# proto.net
KiCad netlist of a schematic drawn in EAGLE
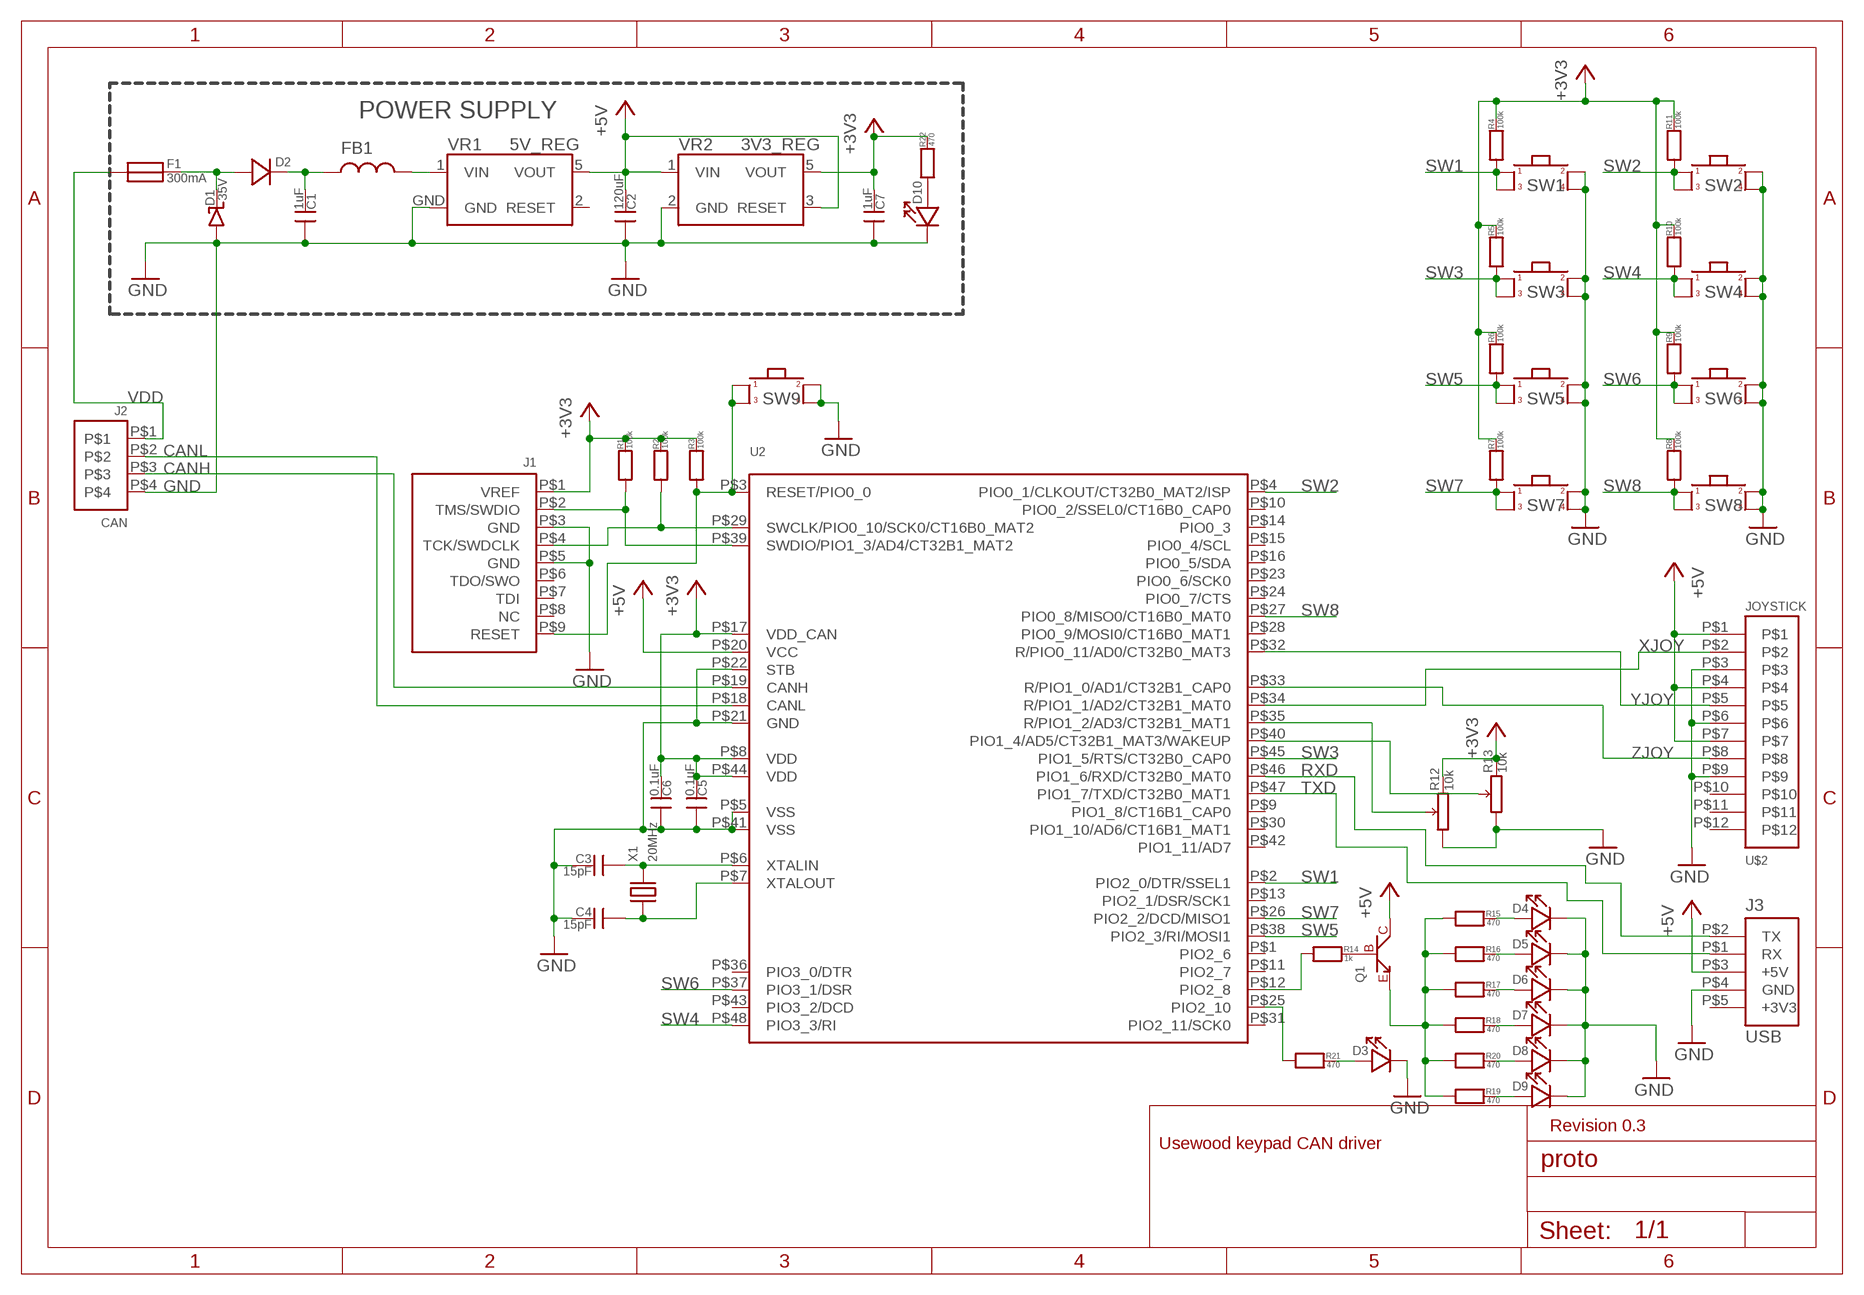
[diagram p0: schematic, sheet 1]

(export (version "E")
  (design (tool "Eeschema 10.0.6"))
  (components
    (comp (ref "C1")
      (value "1uF")
      (footprint "eagle-import:0603")
      (libsource (lib "eagle-import") (part "CAP0603"))
    )
    (comp (ref "C2")
      (value "120uF")
      (footprint "eagle-import:0603")
      (libsource (lib "eagle-import") (part "CAP0603"))
    )
    (comp (ref "C3")
      (value "15pF")
      (footprint "eagle-import:0603")
      (libsource (lib "eagle-import") (part "CAP0603"))
    )
    (comp (ref "C4")
      (value "15pF")
      (footprint "eagle-import:0603")
      (libsource (lib "eagle-import") (part "CAP0603"))
    )
    (comp (ref "C5")
      (value "0.1uF")
      (footprint "eagle-import:0603")
      (libsource (lib "eagle-import") (part "CAP0603"))
    )
    (comp (ref "C6")
      (value "0.1uF")
      (footprint "eagle-import:0603")
      (libsource (lib "eagle-import") (part "CAP0603"))
    )
    (comp (ref "C7")
      (value "1uF")
      (footprint "eagle-import:0603")
      (libsource (lib "eagle-import") (part "CAP0603"))
    )
    (comp (ref "D1")
      (value "35V")
      (footprint "eagle-import:DO-214AB")
      (libsource (lib "eagle-import") (part "DIODE_TVSDO-214AA"))
    )
    (comp (ref "D2")
      (value "DIODEDO219AB")
      (footprint "eagle-import:DO219AB")
      (libsource (lib "eagle-import") (part "DIODEDO219AB"))
    )
    (comp (ref "D3")
      (value "LED0603")
      (footprint "eagle-import:0603")
      (libsource (lib "eagle-import") (part "LED0603"))
    )
    (comp (ref "D4")
      (value "LED0603")
      (footprint "eagle-import:0603")
      (libsource (lib "eagle-import") (part "LED0603"))
    )
    (comp (ref "D5")
      (value "LED0603")
      (footprint "eagle-import:0603")
      (libsource (lib "eagle-import") (part "LED0603"))
    )
    (comp (ref "D6")
      (value "LED0603")
      (footprint "eagle-import:0603")
      (libsource (lib "eagle-import") (part "LED0603"))
    )
    (comp (ref "D7")
      (value "LED0603")
      (footprint "eagle-import:0603")
      (libsource (lib "eagle-import") (part "LED0603"))
    )
    (comp (ref "D8")
      (value "LED0603")
      (footprint "eagle-import:0603")
      (libsource (lib "eagle-import") (part "LED0603"))
    )
    (comp (ref "D9")
      (value "LED0603")
      (footprint "eagle-import:0603")
      (libsource (lib "eagle-import") (part "LED0603"))
    )
    (comp (ref "D10")
      (value "LED0603")
      (footprint "eagle-import:0603")
      (libsource (lib "eagle-import") (part "LED0603"))
    )
    (comp (ref "F1")
      (value "300mA")
      (footprint "eagle-import:FUSE_100MA")
      (libsource (lib "eagle-import") (part "FUSE100MA"))
    )
    (comp (ref "FB1")
      (value "FERRITE0603")
      (footprint "eagle-import:0603")
      (libsource (lib "eagle-import") (part "FERRITE0603"))
    )
    (comp (ref "J1")
      (value "ARM_JTAG/SWD_HEADER_10_PINSMD")
      (footprint "eagle-import:ARM_10_PIN_JTAG_SWD_CONNECTOR")
      (libsource (lib "eagle-import") (part "ARM_JTAG/SWD_HEADER_10_PINSMD"))
    )
    (comp (ref "J2")
      (value "CAN")
      (footprint "eagle-import:MOLEX_MICRO-FIT_4WAY")
      (libsource (lib "eagle-import") (part "MOLEX_MICRO-FIT_4WAYTH"))
    )
    (comp (ref "J3")
      (value "USB")
      (footprint "eagle-import:HEADER5_1")
      (libsource (lib "eagle-import") (part "HEADER_USARTTH"))
    )
    (comp (ref "Q1")
      (value "NPN_TRANSISTORSOT323")
      (footprint "eagle-import:SOT323")
      (libsource (lib "eagle-import") (part "NPN_TRANSISTORSOT323"))
    )
    (comp (ref "R1")
      (value "100k")
      (footprint "eagle-import:0603")
      (libsource (lib "eagle-import") (part "RES0603"))
    )
    (comp (ref "R2")
      (value "100k")
      (footprint "eagle-import:0603")
      (libsource (lib "eagle-import") (part "RES0603"))
    )
    (comp (ref "R3")
      (value "100k")
      (footprint "eagle-import:0603")
      (libsource (lib "eagle-import") (part "RES0603"))
    )
    (comp (ref "R4")
      (value "100k")
      (footprint "eagle-import:0603")
      (libsource (lib "eagle-import") (part "RES0603"))
    )
    (comp (ref "R5")
      (value "100k")
      (footprint "eagle-import:0603")
      (libsource (lib "eagle-import") (part "RES0603"))
    )
    (comp (ref "R6")
      (value "100k")
      (footprint "eagle-import:0603")
      (libsource (lib "eagle-import") (part "RES0603"))
    )
    (comp (ref "R7")
      (value "100k")
      (footprint "eagle-import:0603")
      (libsource (lib "eagle-import") (part "RES0603"))
    )
    (comp (ref "R8")
      (value "100k")
      (footprint "eagle-import:0603")
      (libsource (lib "eagle-import") (part "RES0603"))
    )
    (comp (ref "R9")
      (value "100k")
      (footprint "eagle-import:0603")
      (libsource (lib "eagle-import") (part "RES0603"))
    )
    (comp (ref "R10")
      (value "100k")
      (footprint "eagle-import:0603")
      (libsource (lib "eagle-import") (part "RES0603"))
    )
    (comp (ref "R11")
      (value "100k")
      (footprint "eagle-import:0603")
      (libsource (lib "eagle-import") (part "RES0603"))
    )
    (comp (ref "R12")
      (value "10k")
      (footprint "eagle-import:RES_POT_RK09K1130C94")
      (libsource (lib "eagle-import") (part "RES_POTRK09K1130C94"))
    )
    (comp (ref "R13")
      (value "10k")
      (footprint "eagle-import:RES_POT_RK09K1130C94")
      (libsource (lib "eagle-import") (part "RES_POTRK09K1130C94"))
    )
    (comp (ref "R14")
      (value "1k")
      (footprint "eagle-import:0603")
      (libsource (lib "eagle-import") (part "RES0603"))
    )
    (comp (ref "R15")
      (value "470")
      (footprint "eagle-import:0603")
      (libsource (lib "eagle-import") (part "RES0603"))
    )
    (comp (ref "R16")
      (value "470")
      (footprint "eagle-import:0603")
      (libsource (lib "eagle-import") (part "RES0603"))
    )
    (comp (ref "R17")
      (value "470")
      (footprint "eagle-import:0603")
      (libsource (lib "eagle-import") (part "RES0603"))
    )
    (comp (ref "R18")
      (value "470")
      (footprint "eagle-import:0603")
      (libsource (lib "eagle-import") (part "RES0603"))
    )
    (comp (ref "R19")
      (value "470")
      (footprint "eagle-import:0603")
      (libsource (lib "eagle-import") (part "RES0603"))
    )
    (comp (ref "R20")
      (value "470")
      (footprint "eagle-import:0603")
      (libsource (lib "eagle-import") (part "RES0603"))
    )
    (comp (ref "R21")
      (value "470")
      (footprint "eagle-import:0603")
      (libsource (lib "eagle-import") (part "RES0603"))
    )
    (comp (ref "R22")
      (value "470")
      (footprint "eagle-import:0603")
      (libsource (lib "eagle-import") (part "RES0603"))
    )
    (comp (ref "SW1")
      (value "SWITCH12X12MM_CENTER_HOLE")
      (footprint "eagle-import:SWITCH_12X12MM_CENTER_HOLE")
      (libsource (lib "eagle-import") (part "SWITCH12X12MM_CENTER_HOLE"))
    )
    (comp (ref "SW2")
      (value "SWITCH12X12MM_CENTER_HOLE")
      (footprint "eagle-import:SWITCH_12X12MM_CENTER_HOLE")
      (libsource (lib "eagle-import") (part "SWITCH12X12MM_CENTER_HOLE"))
    )
    (comp (ref "SW3")
      (value "SWITCH12X12MM_CENTER_HOLE")
      (footprint "eagle-import:SWITCH_12X12MM_CENTER_HOLE")
      (libsource (lib "eagle-import") (part "SWITCH12X12MM_CENTER_HOLE"))
    )
    (comp (ref "SW4")
      (value "SWITCH12X12MM_CENTER_HOLE")
      (footprint "eagle-import:SWITCH_12X12MM_CENTER_HOLE")
      (libsource (lib "eagle-import") (part "SWITCH12X12MM_CENTER_HOLE"))
    )
    (comp (ref "SW5")
      (value "SWITCH12X12MM_CENTER_HOLE")
      (footprint "eagle-import:SWITCH_12X12MM_CENTER_HOLE")
      (libsource (lib "eagle-import") (part "SWITCH12X12MM_CENTER_HOLE"))
    )
    (comp (ref "SW6")
      (value "SWITCH12X12MM_CENTER_HOLE")
      (footprint "eagle-import:SWITCH_12X12MM_CENTER_HOLE")
      (libsource (lib "eagle-import") (part "SWITCH12X12MM_CENTER_HOLE"))
    )
    (comp (ref "SW7")
      (value "SWITCH12X12MM_CENTER_HOLE")
      (footprint "eagle-import:SWITCH_12X12MM_CENTER_HOLE")
      (libsource (lib "eagle-import") (part "SWITCH12X12MM_CENTER_HOLE"))
    )
    (comp (ref "SW8")
      (value "SWITCH12X12MM_CENTER_HOLE")
      (footprint "eagle-import:SWITCH_12X12MM_CENTER_HOLE")
      (libsource (lib "eagle-import") (part "SWITCH12X12MM_CENTER_HOLE"))
    )
    (comp (ref "SW9")
      (value "SWITCHREGULAR")
      (footprint "eagle-import:SWITCH_REGULAR")
      (libsource (lib "eagle-import") (part "SWITCHREGULAR"))
    )
    (comp (ref "U$2")
      (value "JOYSTICK")
      (footprint "eagle-import:MOLEX-43045-1000")
      (libsource (lib "eagle-import") (part "HEADER_MOLEX_MICRO-FIT"))
    )
    (comp (ref "U2")
      (value "LPC11C22QFP48")
      (footprint "eagle-import:QFP48")
      (libsource (lib "eagle-import") (part "LPC11C22QFP48"))
    )
    (comp (ref "VR1")
      (value "5V_REG")
      (footprint "eagle-import:175AA")
      (libsource (lib "eagle-import") (part "NCV8675175AA"))
    )
    (comp (ref "VR2")
      (value "3V3_REG")
      (footprint "eagle-import:SOP5")
      (libsource (lib "eagle-import") (part "LP2985SOP5"))
    )
    (comp (ref "X1")
      (value "20MHz")
      (footprint "eagle-import:XTAL_SMD_5X3.2")
      (libsource (lib "eagle-import") (part "XTALSMD_5X3.2"))
    )
  )
  (nets
    (net (code "1") (name "+3V3") (class "Default")
      (node (ref "C5") (pin "1") (pinfunction "P$2_1") (pintype "bidirectional"))
      (node (ref "C6") (pin "1") (pinfunction "P$2_1") (pintype "bidirectional"))
      (node (ref "C7") (pin "1") (pinfunction "P$2_1") (pintype "bidirectional"))
      (node (ref "J1") (pin "P$1") (pinfunction "VREF_P$1") (pintype "bidirectional"))
      (node (ref "R1") (pin "1") (pinfunction "P$2_1") (pintype "bidirectional"))
      (node (ref "R10") (pin "1") (pinfunction "P$2_1") (pintype "bidirectional"))
      (node (ref "R11") (pin "1") (pinfunction "P$2_1") (pintype "bidirectional"))
      (node (ref "R12") (pin "P$3") (pinfunction "P$2_P$3") (pintype "bidirectional"))
      (node (ref "R13") (pin "P$3") (pinfunction "P$2_P$3") (pintype "bidirectional"))
      (node (ref "R2") (pin "1") (pinfunction "P$2_1") (pintype "bidirectional"))
      (node (ref "R22") (pin "1") (pinfunction "P$2_1") (pintype "bidirectional"))
      (node (ref "R3") (pin "1") (pinfunction "P$2_1") (pintype "bidirectional"))
      (node (ref "R4") (pin "1") (pinfunction "P$2_1") (pintype "bidirectional"))
      (node (ref "R5") (pin "1") (pinfunction "P$2_1") (pintype "bidirectional"))
      (node (ref "R6") (pin "1") (pinfunction "P$2_1") (pintype "bidirectional"))
      (node (ref "R7") (pin "1") (pinfunction "P$2_1") (pintype "bidirectional"))
      (node (ref "R8") (pin "1") (pinfunction "P$2_1") (pintype "bidirectional"))
      (node (ref "R9") (pin "1") (pinfunction "P$2_1") (pintype "bidirectional"))
      (node (ref "U2") (pin "P$17") (pinfunction "VDD_CAN_P$17") (pintype "bidirectional"))
      (node (ref "U2") (pin "P$44") (pinfunction "VDD_P$44") (pintype "bidirectional"))
      (node (ref "U2") (pin "P$8") (pinfunction "VDD_P$8") (pintype "bidirectional"))
      (node (ref "VR2") (pin "5") (pinfunction "VOUT_5") (pintype "bidirectional"))
    )
    (net (code "2") (name "+5V") (class "Default")
      (node (ref "C2") (pin "1") (pinfunction "P$2_1") (pintype "bidirectional"))
      (node (ref "J3") (pin "P$3") (pinfunction "+5V_P$3") (pintype "bidirectional"))
      (node (ref "Q1") (pin "M") (pinfunction "C_M") (pintype "bidirectional"))
      (node (ref "U$2") (pin "P$1") (pinfunction "P$1_P$1") (pintype "bidirectional"))
      (node (ref "U$2") (pin "P$4") (pinfunction "P$4_P$4") (pintype "bidirectional"))
      (node (ref "U$2") (pin "P$7") (pinfunction "P$7_P$7") (pintype "bidirectional"))
      (node (ref "U2") (pin "P$20") (pinfunction "VCC_P$20") (pintype "bidirectional"))
      (node (ref "VR1") (pin "5") (pinfunction "VOUT_5") (pintype "bidirectional"))
      (node (ref "VR2") (pin "1") (pinfunction "VIN_1") (pintype "bidirectional"))
      (node (ref "VR2") (pin "3") (pinfunction "RESET_3") (pintype "bidirectional"))
    )
    (net (code "3") (name "/CANH") (class "Default")
      (node (ref "J2") (pin "P$3") (pinfunction "P$3_P$3") (pintype "bidirectional"))
      (node (ref "U2") (pin "P$19") (pinfunction "CANH_P$19") (pintype "bidirectional"))
    )
    (net (code "4") (name "/CANL") (class "Default")
      (node (ref "J2") (pin "P$2") (pinfunction "P$2_P$2") (pintype "bidirectional"))
      (node (ref "U2") (pin "P$18") (pinfunction "CANL_P$18") (pintype "bidirectional"))
    )
    (net (code "5") (name "/RXD") (class "Default")
      (node (ref "J3") (pin "P$2") (pinfunction "TX_P$2") (pintype "bidirectional"))
      (node (ref "U2") (pin "P$46") (pinfunction "PIO1_6/RXD/CT32B0_MAT0_P$46") (pintype "bidirectional"))
    )
    (net (code "6") (name "/SW1") (class "Default")
      (node (ref "R4") (pin "0") (pinfunction "P$1_0") (pintype "bidirectional"))
      (node (ref "SW1") (pin "P$1") (pinfunction "P$1_P$1") (pintype "bidirectional"))
      (node (ref "SW1") (pin "P$2") (pinfunction "P$3_P$2") (pintype "bidirectional"))
      (node (ref "U2") (pin "P$2") (pinfunction "PIO2_0/DTR/SSEL1_P$2") (pintype "bidirectional"))
    )
    (net (code "7") (name "/SW2") (class "Default")
      (node (ref "R11") (pin "0") (pinfunction "P$1_0") (pintype "bidirectional"))
      (node (ref "SW2") (pin "P$1") (pinfunction "P$1_P$1") (pintype "bidirectional"))
      (node (ref "SW2") (pin "P$2") (pinfunction "P$3_P$2") (pintype "bidirectional"))
      (node (ref "U2") (pin "P$4") (pinfunction "PIO0_1/CLKOUT/CT32B0_MAT2/ISP_P$4") (pintype "bidirectional"))
    )
    (net (code "8") (name "/SW3") (class "Default")
      (node (ref "R5") (pin "0") (pinfunction "P$1_0") (pintype "bidirectional"))
      (node (ref "SW3") (pin "P$1") (pinfunction "P$1_P$1") (pintype "bidirectional"))
      (node (ref "SW3") (pin "P$2") (pinfunction "P$3_P$2") (pintype "bidirectional"))
      (node (ref "U2") (pin "P$45") (pinfunction "PIO1_5/RTS/CT32B0_CAP0_P$45") (pintype "bidirectional"))
    )
    (net (code "9") (name "/SW4") (class "Default")
      (node (ref "R10") (pin "0") (pinfunction "P$1_0") (pintype "bidirectional"))
      (node (ref "SW4") (pin "P$1") (pinfunction "P$1_P$1") (pintype "bidirectional"))
      (node (ref "SW4") (pin "P$2") (pinfunction "P$3_P$2") (pintype "bidirectional"))
      (node (ref "U2") (pin "P$48") (pinfunction "PIO3_3/RI_P$48") (pintype "bidirectional"))
    )
    (net (code "10") (name "/SW5") (class "Default")
      (node (ref "R6") (pin "0") (pinfunction "P$1_0") (pintype "bidirectional"))
      (node (ref "SW5") (pin "P$1") (pinfunction "P$1_P$1") (pintype "bidirectional"))
      (node (ref "SW5") (pin "P$2") (pinfunction "P$3_P$2") (pintype "bidirectional"))
      (node (ref "U2") (pin "P$38") (pinfunction "PIO2_3/RI/MOSI1_P$38") (pintype "bidirectional"))
    )
    (net (code "11") (name "/SW6") (class "Default")
      (node (ref "R9") (pin "0") (pinfunction "P$1_0") (pintype "bidirectional"))
      (node (ref "SW6") (pin "P$1") (pinfunction "P$1_P$1") (pintype "bidirectional"))
      (node (ref "SW6") (pin "P$2") (pinfunction "P$3_P$2") (pintype "bidirectional"))
      (node (ref "U2") (pin "P$37") (pinfunction "PIO3_1/DSR_P$37") (pintype "bidirectional"))
    )
    (net (code "12") (name "/SW7") (class "Default")
      (node (ref "R7") (pin "0") (pinfunction "P$1_0") (pintype "bidirectional"))
      (node (ref "SW7") (pin "P$1") (pinfunction "P$1_P$1") (pintype "bidirectional"))
      (node (ref "SW7") (pin "P$2") (pinfunction "P$3_P$2") (pintype "bidirectional"))
      (node (ref "U2") (pin "P$26") (pinfunction "PIO2_2/DCD/MISO1_P$26") (pintype "bidirectional"))
    )
    (net (code "13") (name "/SW8") (class "Default")
      (node (ref "R8") (pin "0") (pinfunction "P$1_0") (pintype "bidirectional"))
      (node (ref "SW8") (pin "P$1") (pinfunction "P$1_P$1") (pintype "bidirectional"))
      (node (ref "SW8") (pin "P$2") (pinfunction "P$3_P$2") (pintype "bidirectional"))
      (node (ref "U2") (pin "P$27") (pinfunction "PIO0_8/MISO0/CT16B0_MAT0_P$27") (pintype "bidirectional"))
    )
    (net (code "14") (name "/TXD") (class "Default")
      (node (ref "J3") (pin "P$1") (pinfunction "RX_P$1") (pintype "bidirectional"))
      (node (ref "U2") (pin "P$47") (pinfunction "PIO1_7/TXD/CT32B0_MAT1_P$47") (pintype "bidirectional"))
    )
    (net (code "15") (name "/VDD") (class "Default")
      (node (ref "F1") (pin "P$1") (pinfunction "P$1_P$1") (pintype "bidirectional"))
      (node (ref "J2") (pin "P$1") (pinfunction "P$1_P$1") (pintype "bidirectional"))
    )
    (net (code "16") (name "/XJOY") (class "Default")
      (node (ref "U$2") (pin "P$2") (pinfunction "P$2_P$2") (pintype "bidirectional"))
      (node (ref "U2") (pin "P$34") (pinfunction "R/PIO1_1/AD2/CT32B1_MAT0_P$34") (pintype "bidirectional"))
    )
    (net (code "17") (name "/YJOY") (class "Default")
      (node (ref "U$2") (pin "P$5") (pinfunction "P$5_P$5") (pintype "bidirectional"))
      (node (ref "U2") (pin "P$32") (pinfunction "R/PIO0_11/AD0/CT32B0_MAT3_P$32") (pintype "bidirectional"))
    )
    (net (code "18") (name "/ZJOY") (class "Default")
      (node (ref "U$2") (pin "P$8") (pinfunction "P$8_P$8") (pintype "bidirectional"))
      (node (ref "U2") (pin "P$33") (pinfunction "R/PIO1_0/AD1/CT32B1_CAP0_P$33") (pintype "bidirectional"))
    )
    (net (code "19") (name "GND") (class "Default")
      (node (ref "C1") (pin "0") (pinfunction "P$1_0") (pintype "bidirectional"))
      (node (ref "C2") (pin "0") (pinfunction "P$1_0") (pintype "bidirectional"))
      (node (ref "C3") (pin "1") (pinfunction "P$2_1") (pintype "bidirectional"))
      (node (ref "C4") (pin "1") (pinfunction "P$2_1") (pintype "bidirectional"))
      (node (ref "C5") (pin "0") (pinfunction "P$1_0") (pintype "bidirectional"))
      (node (ref "C6") (pin "0") (pinfunction "P$1_0") (pintype "bidirectional"))
      (node (ref "C7") (pin "0") (pinfunction "P$1_0") (pintype "bidirectional"))
      (node (ref "D1") (pin "P$1") (pinfunction "P_P$1") (pintype "bidirectional"))
      (node (ref "D10") (pin "1") (pinfunction "1_1") (pintype "bidirectional"))
      (node (ref "D3") (pin "1") (pinfunction "1_1") (pintype "bidirectional"))
      (node (ref "D4") (pin "1") (pinfunction "1_1") (pintype "bidirectional"))
      (node (ref "D5") (pin "1") (pinfunction "1_1") (pintype "bidirectional"))
      (node (ref "D6") (pin "1") (pinfunction "1_1") (pintype "bidirectional"))
      (node (ref "D7") (pin "1") (pinfunction "1_1") (pintype "bidirectional"))
      (node (ref "D8") (pin "1") (pinfunction "1_1") (pintype "bidirectional"))
      (node (ref "D9") (pin "1") (pinfunction "1_1") (pintype "bidirectional"))
      (node (ref "J1") (pin "P$3") (pinfunction "GND_P$3") (pintype "bidirectional"))
      (node (ref "J1") (pin "P$5") (pinfunction "GND_P$5") (pintype "bidirectional"))
      (node (ref "J2") (pin "P$4") (pinfunction "P$4_P$4") (pintype "bidirectional"))
      (node (ref "J3") (pin "P$4") (pinfunction "GND_P$4") (pintype "bidirectional"))
      (node (ref "R12") (pin "P$1") (pinfunction "P$1_P$1") (pintype "bidirectional"))
      (node (ref "R13") (pin "P$1") (pinfunction "P$1_P$1") (pintype "bidirectional"))
      (node (ref "SW1") (pin "P$3") (pinfunction "P$2_P$3") (pintype "bidirectional"))
      (node (ref "SW1") (pin "P$4") (pinfunction "P$4_P$4") (pintype "bidirectional"))
      (node (ref "SW2") (pin "P$3") (pinfunction "P$2_P$3") (pintype "bidirectional"))
      (node (ref "SW2") (pin "P$4") (pinfunction "P$4_P$4") (pintype "bidirectional"))
      (node (ref "SW3") (pin "P$3") (pinfunction "P$2_P$3") (pintype "bidirectional"))
      (node (ref "SW3") (pin "P$4") (pinfunction "P$4_P$4") (pintype "bidirectional"))
      (node (ref "SW4") (pin "P$3") (pinfunction "P$2_P$3") (pintype "bidirectional"))
      (node (ref "SW4") (pin "P$4") (pinfunction "P$4_P$4") (pintype "bidirectional"))
      (node (ref "SW5") (pin "P$3") (pinfunction "P$2_P$3") (pintype "bidirectional"))
      (node (ref "SW5") (pin "P$4") (pinfunction "P$4_P$4") (pintype "bidirectional"))
      (node (ref "SW6") (pin "P$3") (pinfunction "P$2_P$3") (pintype "bidirectional"))
      (node (ref "SW6") (pin "P$4") (pinfunction "P$4_P$4") (pintype "bidirectional"))
      (node (ref "SW7") (pin "P$3") (pinfunction "P$2_P$3") (pintype "bidirectional"))
      (node (ref "SW7") (pin "P$4") (pinfunction "P$4_P$4") (pintype "bidirectional"))
      (node (ref "SW8") (pin "P$3") (pinfunction "P$2_P$3") (pintype "bidirectional"))
      (node (ref "SW8") (pin "P$4") (pinfunction "P$4_P$4") (pintype "bidirectional"))
      (node (ref "SW9") (pin "P$3") (pinfunction "P$4_P$3") (pintype "bidirectional"))
      (node (ref "SW9") (pin "P$4") (pinfunction "P$2_P$4") (pintype "bidirectional"))
      (node (ref "U$2") (pin "P$3") (pinfunction "P$3_P$3") (pintype "bidirectional"))
      (node (ref "U$2") (pin "P$6") (pinfunction "P$6_P$6") (pintype "bidirectional"))
      (node (ref "U$2") (pin "P$9") (pinfunction "P$9_P$9") (pintype "bidirectional"))
      (node (ref "U2") (pin "P$21") (pinfunction "GND_P$21") (pintype "bidirectional"))
      (node (ref "U2") (pin "P$22") (pinfunction "STB_P$22") (pintype "bidirectional"))
      (node (ref "U2") (pin "P$41") (pinfunction "VSS_P$41") (pintype "bidirectional"))
      (node (ref "U2") (pin "P$5") (pinfunction "VSS_P$5") (pintype "bidirectional"))
      (node (ref "VR1") (pin "GND") (pinfunction "GND_GND") (pintype "bidirectional"))
      (node (ref "VR2") (pin "2") (pinfunction "GND_2") (pintype "bidirectional"))
    )
    (net (code "20") (name "Net-(C1-P$2)") (class "Default")
      (node (ref "C1") (pin "1") (pinfunction "P$2_1") (pintype "bidirectional"))
      (node (ref "D2") (pin "P$2") (pinfunction "N_P$2") (pintype "bidirectional"))
      (node (ref "FB1") (pin "0") (pinfunction "P$1_0") (pintype "bidirectional"))
    )
    (net (code "21") (name "Net-(C3-P$1)") (class "Default")
      (node (ref "C3") (pin "0") (pinfunction "P$1_0") (pintype "bidirectional"))
      (node (ref "U2") (pin "P$6") (pinfunction "XTALIN_P$6") (pintype "bidirectional"))
      (node (ref "X1") (pin "P$2") (pinfunction "P$2_P$2") (pintype "bidirectional"))
    )
    (net (code "22") (name "Net-(C4-P$1)") (class "Default")
      (node (ref "C4") (pin "0") (pinfunction "P$1_0") (pintype "bidirectional"))
      (node (ref "U2") (pin "P$7") (pinfunction "XTALOUT_P$7") (pintype "bidirectional"))
      (node (ref "X1") (pin "P$1") (pinfunction "P$1_P$1") (pintype "bidirectional"))
    )
    (net (code "23") (name "Net-(D1-N)") (class "Default")
      (node (ref "D1") (pin "P$2") (pinfunction "N_P$2") (pintype "bidirectional"))
      (node (ref "D2") (pin "P$1") (pinfunction "P_P$1") (pintype "bidirectional"))
      (node (ref "F1") (pin "P$2") (pinfunction "P$2_P$2") (pintype "bidirectional"))
    )
    (net (code "24") (name "Net-(FB1-P$2)") (class "Default")
      (node (ref "FB1") (pin "1") (pinfunction "P$2_1") (pintype "bidirectional"))
      (node (ref "VR1") (pin "1") (pinfunction "VIN_1") (pintype "bidirectional"))
    )
    (net (code "25") (name "Net-(J1-RESET)") (class "Default")
      (node (ref "J1") (pin "P$9") (pinfunction "RESET_P$9") (pintype "bidirectional"))
      (node (ref "R3") (pin "0") (pinfunction "P$1_0") (pintype "bidirectional"))
      (node (ref "SW9") (pin "P$1") (pinfunction "P$1_P$1") (pintype "bidirectional"))
      (node (ref "SW9") (pin "P$2") (pinfunction "P$3_P$2") (pintype "bidirectional"))
      (node (ref "U2") (pin "P$3") (pinfunction "RESET/PIO0_0_P$3") (pintype "bidirectional"))
    )
    (net (code "26") (name "Net-(J1-TCK{slash}SWDCLK)") (class "Default")
      (node (ref "J1") (pin "P$4") (pinfunction "TCK/SWDCLK_P$4") (pintype "bidirectional"))
      (node (ref "R2") (pin "0") (pinfunction "P$1_0") (pintype "bidirectional"))
      (node (ref "U2") (pin "P$29") (pinfunction "SWCLK/PIO0_10/SCK0/CT16B0_MAT2_P$29") (pintype "bidirectional"))
    )
    (net (code "27") (name "Net-(J1-TMS{slash}SWDIO)") (class "Default")
      (node (ref "J1") (pin "P$2") (pinfunction "TMS/SWDIO_P$2") (pintype "bidirectional"))
      (node (ref "R1") (pin "0") (pinfunction "P$1_0") (pintype "bidirectional"))
      (node (ref "U2") (pin "P$39") (pinfunction "SWDIO/PIO1_3/AD4/CT32B1_MAT2_P$39") (pintype "bidirectional"))
    )
    (net (code "28") (name "Net-(Q1-B)") (class "Default")
      (node (ref "Q1") (pin "L") (pinfunction "B_L") (pintype "bidirectional"))
      (node (ref "R14") (pin "1") (pinfunction "P$2_1") (pintype "bidirectional"))
    )
    (net (code "29") (name "Net-(Q1-E)") (class "Default")
      (node (ref "Q1") (pin "R") (pinfunction "E_R") (pintype "bidirectional"))
      (node (ref "R15") (pin "0") (pinfunction "P$1_0") (pintype "bidirectional"))
      (node (ref "R16") (pin "0") (pinfunction "P$1_0") (pintype "bidirectional"))
      (node (ref "R17") (pin "0") (pinfunction "P$1_0") (pintype "bidirectional"))
      (node (ref "R18") (pin "0") (pinfunction "P$1_0") (pintype "bidirectional"))
      (node (ref "R19") (pin "0") (pinfunction "P$1_0") (pintype "bidirectional"))
      (node (ref "R20") (pin "0") (pinfunction "P$1_0") (pintype "bidirectional"))
    )
    (net (code "30") (name "Net-(R12-P$3)") (class "Default")
      (node (ref "R12") (pin "P$2") (pinfunction "P$3_P$2") (pintype "bidirectional"))
      (node (ref "U2") (pin "P$35") (pinfunction "R/PIO1_2/AD3/CT32B1_MAT1_P$35") (pintype "bidirectional"))
    )
    (net (code "31") (name "Net-(R13-P$3)") (class "Default")
      (node (ref "R13") (pin "P$2") (pinfunction "P$3_P$2") (pintype "bidirectional"))
      (node (ref "U2") (pin "P$40") (pinfunction "PIO1_4/AD5/CT32B1_MAT3/WAKEUP_P$40") (pintype "bidirectional"))
    )
    (net (code "32") (name "Net-(R14-P$1)") (class "Default")
      (node (ref "R14") (pin "0") (pinfunction "P$1_0") (pintype "bidirectional"))
      (node (ref "U2") (pin "P$12") (pinfunction "PIO2_8_P$12") (pintype "bidirectional"))
    )
    (net (code "33") (name "Net-(R15-P$2)") (class "Default")
      (node (ref "D4") (pin "0") (pinfunction "0_0") (pintype "bidirectional"))
      (node (ref "R15") (pin "1") (pinfunction "P$2_1") (pintype "bidirectional"))
    )
    (net (code "34") (name "Net-(R16-P$2)") (class "Default")
      (node (ref "D5") (pin "0") (pinfunction "0_0") (pintype "bidirectional"))
      (node (ref "R16") (pin "1") (pinfunction "P$2_1") (pintype "bidirectional"))
    )
    (net (code "35") (name "Net-(R17-P$2)") (class "Default")
      (node (ref "D6") (pin "0") (pinfunction "0_0") (pintype "bidirectional"))
      (node (ref "R17") (pin "1") (pinfunction "P$2_1") (pintype "bidirectional"))
    )
    (net (code "36") (name "Net-(R18-P$2)") (class "Default")
      (node (ref "D7") (pin "0") (pinfunction "0_0") (pintype "bidirectional"))
      (node (ref "R18") (pin "1") (pinfunction "P$2_1") (pintype "bidirectional"))
    )
    (net (code "37") (name "Net-(R19-P$2)") (class "Default")
      (node (ref "D9") (pin "0") (pinfunction "0_0") (pintype "bidirectional"))
      (node (ref "R19") (pin "1") (pinfunction "P$2_1") (pintype "bidirectional"))
    )
    (net (code "38") (name "Net-(R20-P$2)") (class "Default")
      (node (ref "D8") (pin "0") (pinfunction "0_0") (pintype "bidirectional"))
      (node (ref "R20") (pin "1") (pinfunction "P$2_1") (pintype "bidirectional"))
    )
    (net (code "39") (name "Net-(R21-P$1)") (class "Default")
      (node (ref "R21") (pin "0") (pinfunction "P$1_0") (pintype "bidirectional"))
      (node (ref "U2") (pin "P$25") (pinfunction "PIO2_10_P$25") (pintype "bidirectional"))
    )
    (net (code "40") (name "Net-(R21-P$2)") (class "Default")
      (node (ref "D3") (pin "0") (pinfunction "0_0") (pintype "bidirectional"))
      (node (ref "R21") (pin "1") (pinfunction "P$2_1") (pintype "bidirectional"))
    )
    (net (code "41") (name "Net-(R22-P$1)") (class "Default")
      (node (ref "D10") (pin "0") (pinfunction "0_0") (pintype "bidirectional"))
      (node (ref "R22") (pin "0") (pinfunction "P$1_0") (pintype "bidirectional"))
    )
    (net (code "42") (name "unconnected-(J1-NC-PadP$8)") (class "Default")
      (node (ref "J1") (pin "P$8") (pinfunction "NC_P$8") (pintype "bidirectional"))
    )
    (net (code "43") (name "unconnected-(J1-TDI-PadP$7)") (class "Default")
      (node (ref "J1") (pin "P$7") (pinfunction "TDI_P$7") (pintype "bidirectional"))
    )
    (net (code "44") (name "unconnected-(J1-TDO{slash}SWO-PadP$6)") (class "Default")
      (node (ref "J1") (pin "P$6") (pinfunction "TDO/SWO_P$6") (pintype "bidirectional"))
    )
    (net (code "45") (name "unconnected-(J3-+3V3-PadP$5)") (class "Default")
      (node (ref "J3") (pin "P$5") (pinfunction "+3V3_P$5") (pintype "bidirectional"))
    )
    (net (code "46") (name "unconnected-(U$2-PadP$10)") (class "Default")
      (node (ref "U$2") (pin "P$10") (pinfunction "P$10_P$10") (pintype "bidirectional"))
    )
    (net (code "47") (name "unconnected-(U$2-PadP$11)") (class "Default")
      (node (ref "U$2") (pin "P$11") (pinfunction "P$11_P$11") (pintype "bidirectional"))
    )
    (net (code "48") (name "unconnected-(U$2-PadP$12)") (class "Default")
      (node (ref "U$2") (pin "P$12") (pinfunction "P$12_P$12") (pintype "bidirectional"))
    )
    (net (code "49") (name "unconnected-(U2-PIO0_2{slash}SSEL0{slash}CT16B0_CAP0-PadP$10)") (class "Default")
      (node (ref "U2") (pin "P$10") (pinfunction "PIO0_2/SSEL0/CT16B0_CAP0_P$10") (pintype "bidirectional"))
    )
    (net (code "50") (name "unconnected-(U2-PIO0_3-PadP$14)") (class "Default")
      (node (ref "U2") (pin "P$14") (pinfunction "PIO0_3_P$14") (pintype "bidirectional"))
    )
    (net (code "51") (name "unconnected-(U2-PIO0_4{slash}SCL-PadP$15)") (class "Default")
      (node (ref "U2") (pin "P$15") (pinfunction "PIO0_4/SCL_P$15") (pintype "bidirectional"))
    )
    (net (code "52") (name "unconnected-(U2-PIO0_5{slash}SDA-PadP$16)") (class "Default")
      (node (ref "U2") (pin "P$16") (pinfunction "PIO0_5/SDA_P$16") (pintype "bidirectional"))
    )
    (net (code "53") (name "unconnected-(U2-PIO0_6{slash}SCK0-PadP$23)") (class "Default")
      (node (ref "U2") (pin "P$23") (pinfunction "PIO0_6/SCK0_P$23") (pintype "bidirectional"))
    )
    (net (code "54") (name "unconnected-(U2-PIO0_7{slash}CTS-PadP$24)") (class "Default")
      (node (ref "U2") (pin "P$24") (pinfunction "PIO0_7/CTS_P$24") (pintype "bidirectional"))
    )
    (net (code "55") (name "unconnected-(U2-PIO0_9{slash}MOSI0{slash}CT16B0_MAT1-PadP$28)") (class "Default")
      (node (ref "U2") (pin "P$28") (pinfunction "PIO0_9/MOSI0/CT16B0_MAT1_P$28") (pintype "bidirectional"))
    )
    (net (code "56") (name "unconnected-(U2-PIO1_8{slash}CT16B1_CAP0-PadP$9)") (class "Default")
      (node (ref "U2") (pin "P$9") (pinfunction "PIO1_8/CT16B1_CAP0_P$9") (pintype "bidirectional"))
    )
    (net (code "57") (name "unconnected-(U2-PIO1_10{slash}AD6{slash}CT16B1_MAT1-PadP$30)") (class "Default")
      (node (ref "U2") (pin "P$30") (pinfunction "PIO1_10/AD6/CT16B1_MAT1_P$30") (pintype "bidirectional"))
    )
    (net (code "58") (name "unconnected-(U2-PIO1_11{slash}AD7-PadP$42)") (class "Default")
      (node (ref "U2") (pin "P$42") (pinfunction "PIO1_11/AD7_P$42") (pintype "bidirectional"))
    )
    (net (code "59") (name "unconnected-(U2-PIO2_1{slash}DSR{slash}SCK1-PadP$13)") (class "Default")
      (node (ref "U2") (pin "P$13") (pinfunction "PIO2_1/DSR/SCK1_P$13") (pintype "bidirectional"))
    )
    (net (code "60") (name "unconnected-(U2-PIO2_6-PadP$1)") (class "Default")
      (node (ref "U2") (pin "P$1") (pinfunction "PIO2_6_P$1") (pintype "bidirectional"))
    )
    (net (code "61") (name "unconnected-(U2-PIO2_7-PadP$11)") (class "Default")
      (node (ref "U2") (pin "P$11") (pinfunction "PIO2_7_P$11") (pintype "bidirectional"))
    )
    (net (code "62") (name "unconnected-(U2-PIO2_11{slash}SCK0-PadP$31)") (class "Default")
      (node (ref "U2") (pin "P$31") (pinfunction "PIO2_11/SCK0_P$31") (pintype "bidirectional"))
    )
    (net (code "63") (name "unconnected-(U2-PIO3_0{slash}DTR-PadP$36)") (class "Default")
      (node (ref "U2") (pin "P$36") (pinfunction "PIO3_0/DTR_P$36") (pintype "bidirectional"))
    )
    (net (code "64") (name "unconnected-(U2-PIO3_2{slash}DCD-PadP$43)") (class "Default")
      (node (ref "U2") (pin "P$43") (pinfunction "PIO3_2/DCD_P$43") (pintype "bidirectional"))
    )
    (net (code "65") (name "unconnected-(VR1-RESET-Pad2)") (class "Default")
      (node (ref "VR1") (pin "2") (pinfunction "RESET_2") (pintype "bidirectional"))
    )
  )
)
